# USB.net
KiCad netlist of a schematic drawn in Altium Designer
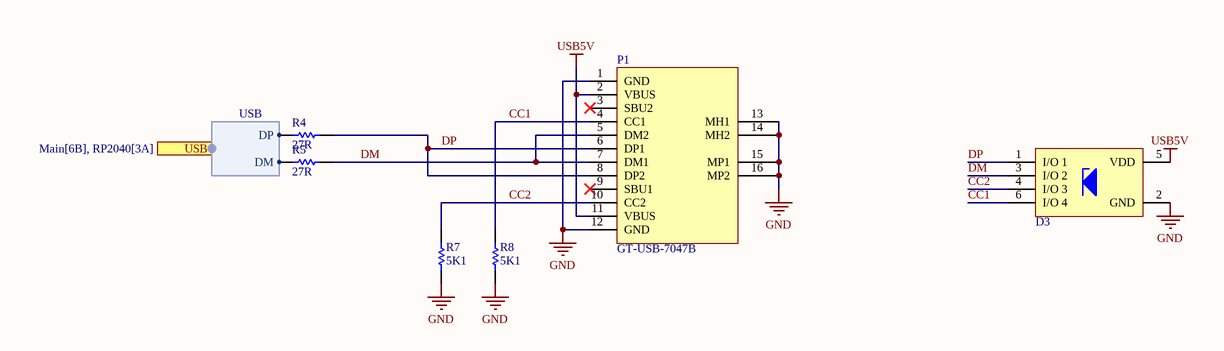
[diagram p0: USB.SchDoc]

(export (version "E")
  (design (tool "Eeschema 10.0.6"))
  (components
    (comp (ref "D3")
      (value "3.3V")
      (footprint "WE-TVS_SOT23-6L")
      (description "WE-TVS TVS Diode – High Speed Series, SOT23-6L, 4+1 Channel, 3.3V, 2pF")
      (fields
        (field (name "MANUFACTURER PART NUMBER") "824015043")
        (field (name "MANUFACTURER") "Wurth Elektronik")
      )
      (libsource (lib "Altium_WE-TVS (rev22b)") (part "824015043"))
    )
    (comp (ref "P1")
      (value "GT-USB-7047B")
      (footprint "GT-USB-7047B")
      (libsource (lib "Custom Components") (part "GT-USB-7047B"))
    )
    (comp (ref "R4")
      (value "27R")
      (footprint "RESC0603(1608)_N")
      (description "Chipwiderstand, Oberflächenmontage, Dickschicht, 27 ohm, 50 V, 0603 [Metrisch 1608], 100 mW, ± 1%")
      (fields (field (name "MANUFACTURER") "Multicomp"))
      (libsource (lib "Standardbauteile") (part "Res 27R"))
    )
    (comp (ref "R5")
      (value "27R")
      (footprint "RESC0603(1608)_N")
      (description "Chipwiderstand, Oberflächenmontage, Dickschicht, 27 ohm, 50 V, 0603 [Metrisch 1608], 100 mW, ± 1%")
      (fields (field (name "MANUFACTURER") "Multicomp"))
      (libsource (lib "Standardbauteile") (part "Res 27R"))
    )
    (comp (ref "R7")
      (value "5K1")
      (footprint "RESC0603(1608)_N")
      (description "Chipwiderstand, SMD, Baureihe MC, 5%")
      (fields (field (name "MANUFACTURER") "Multicomp"))
      (libsource (lib "Standardbauteile") (part "Res 5K6"))
    )
    (comp (ref "R8")
      (value "5K1")
      (footprint "RESC0603(1608)_N")
      (description "Chipwiderstand, SMD, Baureihe MC, 5%")
      (fields (field (name "MANUFACTURER") "Multicomp"))
      (libsource (lib "Standardbauteile") (part "Res 5K6"))
    )
  )
  (nets
    (net (code "2") (name "/CC1") (class "Default")
      (node (ref "D3") (pin "6") (pinfunction "I/O_4_6") (pintype "passive"))
      (node (ref "P1") (pin "4") (pinfunction "CC1_4") (pintype "passive"))
      (node (ref "R8") (pin "2") (pinfunction "2_2") (pintype "passive"))
    )
    (net (code "3") (name "/CC2") (class "Default")
      (node (ref "D3") (pin "4") (pinfunction "I/O_3_4") (pintype "passive"))
      (node (ref "P1") (pin "10") (pinfunction "CC2_10") (pintype "passive"))
      (node (ref "R7") (pin "2") (pinfunction "2_2") (pintype "passive"))
    )
    (net (code "4") (name "/DM") (class "Default")
      (node (ref "D3") (pin "3") (pinfunction "I/O_2_3") (pintype "passive"))
      (node (ref "P1") (pin "5") (pinfunction "DM2_5") (pintype "passive"))
      (node (ref "P1") (pin "7") (pinfunction "DM1_7") (pintype "passive"))
      (node (ref "R5") (pin "2") (pinfunction "2_2") (pintype "passive"))
    )
    (net (code "5") (name "/DP") (class "Default")
      (node (ref "D3") (pin "1") (pinfunction "I/O_1_1") (pintype "passive"))
      (node (ref "P1") (pin "6") (pinfunction "DP1_6") (pintype "passive"))
      (node (ref "P1") (pin "8") (pinfunction "DP2_8") (pintype "passive"))
      (node (ref "R4") (pin "2") (pinfunction "2_2") (pintype "passive"))
    )
    (net (code "7") (name "GND") (class "Default")
      (node (ref "D3") (pin "2") (pinfunction "GND_2") (pintype "passive"))
      (node (ref "P1") (pin "1") (pinfunction "GND_1") (pintype "passive"))
      (node (ref "P1") (pin "12") (pinfunction "GND_12") (pintype "passive"))
      (node (ref "P1") (pin "13") (pinfunction "MH1_13") (pintype "passive"))
      (node (ref "P1") (pin "14") (pinfunction "MH2_14") (pintype "passive"))
      (node (ref "P1") (pin "15") (pinfunction "MP1_15") (pintype "passive"))
      (node (ref "P1") (pin "16") (pinfunction "MP2_16") (pintype "passive"))
      (node (ref "R7") (pin "1") (pinfunction "1_1") (pintype "passive"))
      (node (ref "R8") (pin "1") (pinfunction "1_1") (pintype "passive"))
    )
    (net (code "8") (name "USB5V") (class "Default")
      (node (ref "D3") (pin "5") (pinfunction "VDD_5") (pintype "passive"))
      (node (ref "P1") (pin "11") (pinfunction "VBUS_11") (pintype "passive"))
      (node (ref "P1") (pin "2") (pinfunction "VBUS_2") (pintype "passive"))
    )
    (net (code "9") (name "unconnected-(P1-SBU1-Pad9)") (class "Default")
      (node (ref "P1") (pin "9") (pinfunction "SBU1_9") (pintype "passive+no_connect"))
    )
    (net (code "10") (name "unconnected-(P1-SBU2-Pad3)") (class "Default")
      (node (ref "P1") (pin "3") (pinfunction "SBU2_3") (pintype "passive+no_connect"))
    )
    (net (code "11") (name "unconnected-(R4-Pad1)") (class "Default")
      (node (ref "R4") (pin "1") (pinfunction "1_1") (pintype "passive"))
    )
    (net (code "12") (name "unconnected-(R5-Pad1)") (class "Default")
      (node (ref "R5") (pin "1") (pinfunction "1_1") (pintype "passive"))
    )
  )
)
